# Memory.net
KiCad netlist of a schematic drawn in Altium Designer
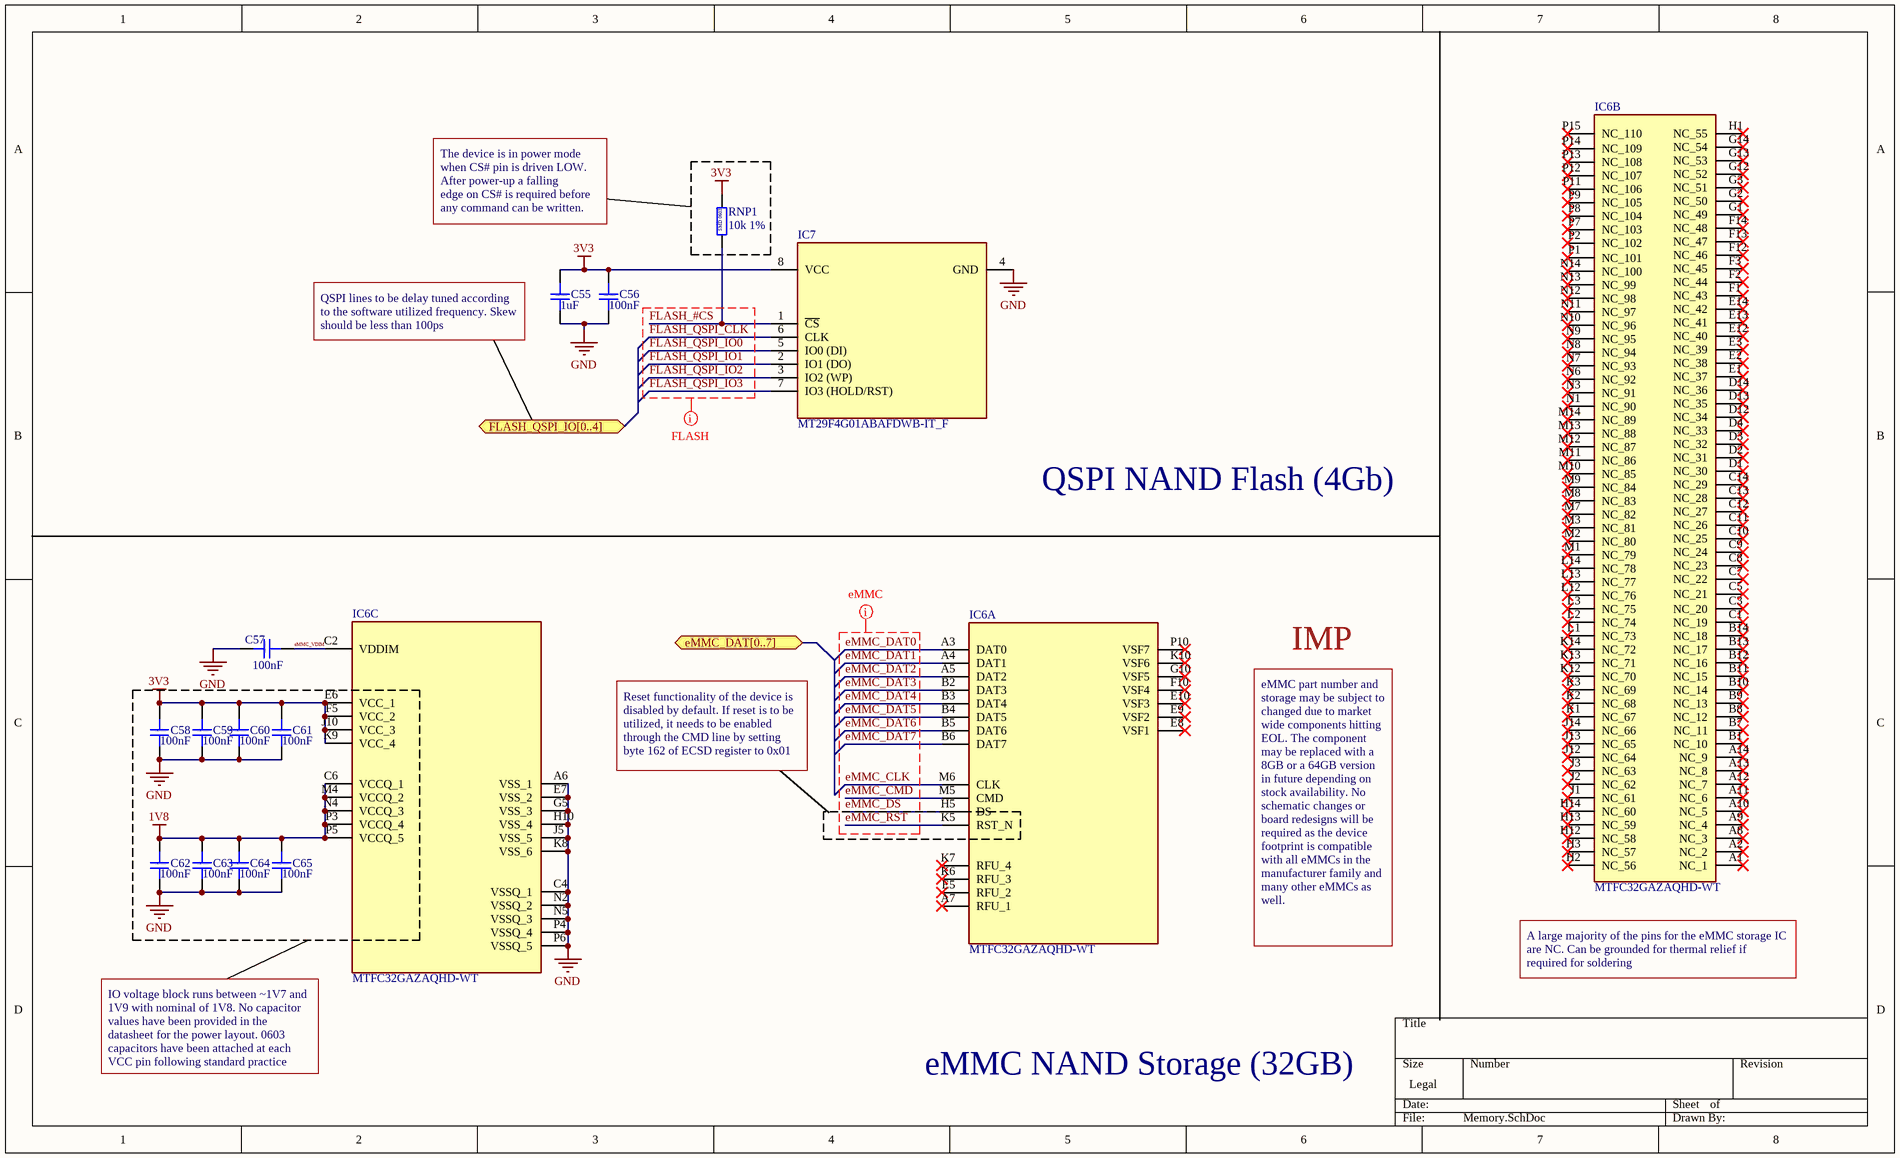
[diagram p0: Memory.SchDoc]

(export (version "E")
  (design (tool "Eeschema 10.0.6"))
  (components
    (comp (ref "C55")
      (value "1uF")
      (footprint "CAP_0402")
      (description "Capacitor SMD 0402 RATED")
      (libsource (lib "STeRG-Passives-Standard") (part "Capacitor-SMD-0402"))
    )
    (comp (ref "C56")
      (value "100nF")
      (footprint "CAP_0402")
      (description "Capacitor SMD 0402 RATED")
      (libsource (lib "STeRG-Passives-Standard") (part "Capacitor-SMD-0402"))
    )
    (comp (ref "C57")
      (value "100nF")
      (footprint "CAP_0402")
      (description "Capacitor SMD 0402 RATED")
      (libsource (lib "STeRG-Passives-Standard") (part "Capacitor-SMD-0402"))
    )
    (comp (ref "C58")
      (value "100nF")
      (footprint "CAP_0402")
      (description "Capacitor SMD 0402 RATED")
      (libsource (lib "STeRG-Passives-Standard") (part "Capacitor-SMD-0402"))
    )
    (comp (ref "C59")
      (value "100nF")
      (footprint "CAP_0402")
      (description "Capacitor SMD 0402 RATED")
      (libsource (lib "STeRG-Passives-Standard") (part "Capacitor-SMD-0402"))
    )
    (comp (ref "C60")
      (value "100nF")
      (footprint "CAP_0402")
      (description "Capacitor SMD 0402 RATED")
      (libsource (lib "STeRG-Passives-Standard") (part "Capacitor-SMD-0402"))
    )
    (comp (ref "C61")
      (value "100nF")
      (footprint "CAP_0402")
      (description "Capacitor SMD 0402 RATED")
      (libsource (lib "STeRG-Passives-Standard") (part "Capacitor-SMD-0402"))
    )
    (comp (ref "C62")
      (value "100nF")
      (footprint "CAP_0402")
      (description "Capacitor SMD 0402 RATED")
      (libsource (lib "STeRG-Passives-Standard") (part "Capacitor-SMD-0402"))
    )
    (comp (ref "C63")
      (value "100nF")
      (footprint "CAP_0402")
      (description "Capacitor SMD 0402 RATED")
      (libsource (lib "STeRG-Passives-Standard") (part "Capacitor-SMD-0402"))
    )
    (comp (ref "C64")
      (value "100nF")
      (footprint "CAP_0402")
      (description "Capacitor SMD 0402 RATED")
      (libsource (lib "STeRG-Passives-Standard") (part "Capacitor-SMD-0402"))
    )
    (comp (ref "C65")
      (value "100nF")
      (footprint "CAP_0402")
      (description "Capacitor SMD 0402 RATED")
      (libsource (lib "STeRG-Passives-Standard") (part "Capacitor-SMD-0402"))
    )
    (comp (ref "IC6")
      (value "MTFC32GAZAQHD-WT")
      (footprint "STeRG-ICs-Standard:BGA153C50P14X14_1150X1300X90")
      (description "Integrated Circuit")
      (fields (field (name "MOUSER PART NUMBER") "340-531307-TRAY"))
      (libsource (lib "") (part "MTFC32GAZAQHD-WT_1"))
    )
    (comp (ref "IC7")
      (value "MT29F4G01ABAFDWB-IT_F")
      (footprint "SON127P800X600X65-8N")
      (description "Integrated Circuit")
      (fields
        (field (name "MANUFACTURER_PART_NUMBER") "MT29F4G01ABAFDWB-IT:F")
        (field (name "MOUSER PART NUMBER") "340-359563")
      )
      (libsource (lib "STeRG-ICs-Standard") (part "MT29F4G01ABAFDWB-IT_F"))
    )
    (comp (ref "RNP1")
      (value "10k 1%")
      (footprint "RES_0603")
      (description "Resistor SMD 0603 RATED")
      (libsource (lib "STeRG-Passives-Standard") (part "Resistor-SMD-0603"))
    )
  )
  (nets
    (net (code "2") (name "/FLASH_#CS") (class "Default")
      (node (ref "IC7") (pin "1") (pinfunction "~{CS}_1") (pintype "passive"))
      (node (ref "RNP1") (pin "1") (pinfunction "1_1") (pintype "passive"))
    )
    (net (code "3") (name "/FLASH_QSPI_CLK") (class "Default")
      (node (ref "IC7") (pin "6") (pinfunction "CLK_6") (pintype "passive"))
    )
    (net (code "4") (name "/FLASH_QSPI_IO0") (class "Default")
      (node (ref "IC7") (pin "5") (pinfunction "IO0_(DI)_5") (pintype "passive"))
    )
    (net (code "5") (name "/FLASH_QSPI_IO1") (class "Default")
      (node (ref "IC7") (pin "2") (pinfunction "IO1_(DO)_2") (pintype "passive"))
    )
    (net (code "6") (name "/FLASH_QSPI_IO2") (class "Default")
      (node (ref "IC7") (pin "3") (pinfunction "IO2_(WP)_3") (pintype "passive"))
    )
    (net (code "7") (name "/FLASH_QSPI_IO3") (class "Default")
      (node (ref "IC7") (pin "7") (pinfunction "IO3_(HOLD/RST)_7") (pintype "passive"))
    )
    (net (code "9") (name "/eMMC_CLK") (class "Default")
      (node (ref "IC6") (pin "M6") (pinfunction "CLK_M6") (pintype "passive"))
    )
    (net (code "10") (name "/eMMC_CMD") (class "Default")
      (node (ref "IC6") (pin "M5") (pinfunction "CMD_M5") (pintype "passive"))
    )
    (net (code "11") (name "/eMMC_DAT0") (class "Default")
      (node (ref "IC6") (pin "A3") (pinfunction "DAT0_A3") (pintype "passive"))
    )
    (net (code "12") (name "/eMMC_DAT1") (class "Default")
      (node (ref "IC6") (pin "A4") (pinfunction "DAT1_A4") (pintype "passive"))
    )
    (net (code "13") (name "/eMMC_DAT2") (class "Default")
      (node (ref "IC6") (pin "A5") (pinfunction "DAT2_A5") (pintype "passive"))
    )
    (net (code "14") (name "/eMMC_DAT3") (class "Default")
      (node (ref "IC6") (pin "B2") (pinfunction "DAT3_B2") (pintype "passive"))
    )
    (net (code "15") (name "/eMMC_DAT4") (class "Default")
      (node (ref "IC6") (pin "B3") (pinfunction "DAT4_B3") (pintype "passive"))
    )
    (net (code "16") (name "/eMMC_DAT5") (class "Default")
      (node (ref "IC6") (pin "B4") (pinfunction "DAT5_B4") (pintype "passive"))
    )
    (net (code "17") (name "/eMMC_DAT6") (class "Default")
      (node (ref "IC6") (pin "B5") (pinfunction "DAT6_B5") (pintype "passive"))
    )
    (net (code "18") (name "/eMMC_DAT7") (class "Default")
      (node (ref "IC6") (pin "B6") (pinfunction "DAT7_B6") (pintype "passive"))
    )
    (net (code "20") (name "/eMMC_DS") (class "Default")
      (node (ref "IC6") (pin "H5") (pinfunction "DS_H5") (pintype "passive"))
    )
    (net (code "21") (name "/eMMC_RST") (class "Default")
      (node (ref "IC6") (pin "K5") (pinfunction "RST_N_K5") (pintype "passive"))
    )
    (net (code "22") (name "/eMMC_VDIM") (class "Default")
      (node (ref "C57") (pin "2") (pinfunction "2_2") (pintype "passive"))
      (node (ref "IC6") (pin "C2") (pinfunction "VDDIM_C2") (pintype "passive"))
    )
    (net (code "23") (name "1V8") (class "Default")
      (node (ref "C62") (pin "1") (pinfunction "1_1") (pintype "passive"))
      (node (ref "C63") (pin "1") (pinfunction "1_1") (pintype "passive"))
      (node (ref "C64") (pin "1") (pinfunction "1_1") (pintype "passive"))
      (node (ref "C65") (pin "1") (pinfunction "1_1") (pintype "passive"))
      (node (ref "IC6") (pin "C6") (pinfunction "VCCQ_1_C6") (pintype "passive"))
      (node (ref "IC6") (pin "M4") (pinfunction "VCCQ_2_M4") (pintype "passive"))
      (node (ref "IC6") (pin "N4") (pinfunction "VCCQ_3_N4") (pintype "passive"))
      (node (ref "IC6") (pin "P3") (pinfunction "VCCQ_4_P3") (pintype "passive"))
      (node (ref "IC6") (pin "P5") (pinfunction "VCCQ_5_P5") (pintype "passive"))
    )
    (net (code "24") (name "3V3") (class "Default")
      (node (ref "C55") (pin "1") (pinfunction "1_1") (pintype "passive"))
      (node (ref "C56") (pin "1") (pinfunction "1_1") (pintype "passive"))
      (node (ref "C58") (pin "1") (pinfunction "1_1") (pintype "passive"))
      (node (ref "C59") (pin "1") (pinfunction "1_1") (pintype "passive"))
      (node (ref "C60") (pin "1") (pinfunction "1_1") (pintype "passive"))
      (node (ref "C61") (pin "1") (pinfunction "1_1") (pintype "passive"))
      (node (ref "IC6") (pin "E6") (pinfunction "VCC_1_E6") (pintype "passive"))
      (node (ref "IC6") (pin "F5") (pinfunction "VCC_2_F5") (pintype "passive"))
      (node (ref "IC6") (pin "J10") (pinfunction "VCC_3_J10") (pintype "passive"))
      (node (ref "IC6") (pin "K9") (pinfunction "VCC_4_K9") (pintype "passive"))
      (node (ref "IC7") (pin "8") (pinfunction "VCC_8") (pintype "passive"))
      (node (ref "RNP1") (pin "2") (pinfunction "2_2") (pintype "passive"))
    )
    (net (code "25") (name "GND") (class "Default")
      (node (ref "C55") (pin "2") (pinfunction "2_2") (pintype "passive"))
      (node (ref "C56") (pin "2") (pinfunction "2_2") (pintype "passive"))
      (node (ref "C57") (pin "1") (pinfunction "1_1") (pintype "passive"))
      (node (ref "C58") (pin "2") (pinfunction "2_2") (pintype "passive"))
      (node (ref "C59") (pin "2") (pinfunction "2_2") (pintype "passive"))
      (node (ref "C60") (pin "2") (pinfunction "2_2") (pintype "passive"))
      (node (ref "C61") (pin "2") (pinfunction "2_2") (pintype "passive"))
      (node (ref "C62") (pin "2") (pinfunction "2_2") (pintype "passive"))
      (node (ref "C63") (pin "2") (pinfunction "2_2") (pintype "passive"))
      (node (ref "C64") (pin "2") (pinfunction "2_2") (pintype "passive"))
      (node (ref "C65") (pin "2") (pinfunction "2_2") (pintype "passive"))
      (node (ref "IC6") (pin "A6") (pinfunction "VSS_1_A6") (pintype "passive"))
      (node (ref "IC6") (pin "C4") (pinfunction "VSSQ_1_C4") (pintype "passive"))
      (node (ref "IC6") (pin "E7") (pinfunction "VSS_2_E7") (pintype "passive"))
      (node (ref "IC6") (pin "G5") (pinfunction "VSS_3_G5") (pintype "passive"))
      (node (ref "IC6") (pin "H10") (pinfunction "VSS_4_H10") (pintype "passive"))
      (node (ref "IC6") (pin "J5") (pinfunction "VSS_5_J5") (pintype "passive"))
      (node (ref "IC6") (pin "K8") (pinfunction "VSS_6_K8") (pintype "passive"))
      (node (ref "IC6") (pin "N2") (pinfunction "VSSQ_2_N2") (pintype "passive"))
      (node (ref "IC6") (pin "N5") (pinfunction "VSSQ_3_N5") (pintype "passive"))
      (node (ref "IC6") (pin "P4") (pinfunction "VSSQ_4_P4") (pintype "passive"))
      (node (ref "IC6") (pin "P6") (pinfunction "VSSQ_5_P6") (pintype "passive"))
      (node (ref "IC7") (pin "4") (pinfunction "GND_4") (pintype "passive"))
    )
    (net (code "26") (name "unconnected-(IC6A-RFU_1-PadA7)") (class "Default")
      (node (ref "IC6") (pin "A7") (pinfunction "RFU_1_A7") (pintype "passive+no_connect"))
    )
    (net (code "27") (name "unconnected-(IC6A-RFU_2-PadE5)") (class "Default")
      (node (ref "IC6") (pin "E5") (pinfunction "RFU_2_E5") (pintype "passive+no_connect"))
    )
    (net (code "28") (name "unconnected-(IC6A-RFU_3-PadK6)") (class "Default")
      (node (ref "IC6") (pin "K6") (pinfunction "RFU_3_K6") (pintype "passive+no_connect"))
    )
    (net (code "29") (name "unconnected-(IC6A-RFU_4-PadK7)") (class "Default")
      (node (ref "IC6") (pin "K7") (pinfunction "RFU_4_K7") (pintype "passive+no_connect"))
    )
    (net (code "30") (name "unconnected-(IC6A-VSF1-PadE8)") (class "Default")
      (node (ref "IC6") (pin "E8") (pinfunction "VSF1_E8") (pintype "passive+no_connect"))
    )
    (net (code "31") (name "unconnected-(IC6A-VSF2-PadE9)") (class "Default")
      (node (ref "IC6") (pin "E9") (pinfunction "VSF2_E9") (pintype "passive+no_connect"))
    )
    (net (code "32") (name "unconnected-(IC6A-VSF3-PadE10)") (class "Default")
      (node (ref "IC6") (pin "E10") (pinfunction "VSF3_E10") (pintype "passive+no_connect"))
    )
    (net (code "33") (name "unconnected-(IC6A-VSF4-PadF10)") (class "Default")
      (node (ref "IC6") (pin "F10") (pinfunction "VSF4_F10") (pintype "passive+no_connect"))
    )
    (net (code "34") (name "unconnected-(IC6A-VSF5-PadG10)") (class "Default")
      (node (ref "IC6") (pin "G10") (pinfunction "VSF5_G10") (pintype "passive+no_connect"))
    )
    (net (code "35") (name "unconnected-(IC6A-VSF6-PadK10)") (class "Default")
      (node (ref "IC6") (pin "K10") (pinfunction "VSF6_K10") (pintype "passive+no_connect"))
    )
    (net (code "36") (name "unconnected-(IC6A-VSF7-PadP10)") (class "Default")
      (node (ref "IC6") (pin "P10") (pinfunction "VSF7_P10") (pintype "passive+no_connect"))
    )
    (net (code "37") (name "unconnected-(IC6B-NC_1-PadA1)") (class "Default")
      (node (ref "IC6") (pin "A1") (pinfunction "NC_1_A1") (pintype "passive+no_connect"))
    )
    (net (code "38") (name "unconnected-(IC6B-NC_2-PadA2)") (class "Default")
      (node (ref "IC6") (pin "A2") (pinfunction "NC_2_A2") (pintype "passive+no_connect"))
    )
    (net (code "39") (name "unconnected-(IC6B-NC_3-PadA8)") (class "Default")
      (node (ref "IC6") (pin "A8") (pinfunction "NC_3_A8") (pintype "passive+no_connect"))
    )
    (net (code "40") (name "unconnected-(IC6B-NC_4-PadA9)") (class "Default")
      (node (ref "IC6") (pin "A9") (pinfunction "NC_4_A9") (pintype "passive+no_connect"))
    )
    (net (code "41") (name "unconnected-(IC6B-NC_5-PadA10)") (class "Default")
      (node (ref "IC6") (pin "A10") (pinfunction "NC_5_A10") (pintype "passive+no_connect"))
    )
    (net (code "42") (name "unconnected-(IC6B-NC_6-PadA11)") (class "Default")
      (node (ref "IC6") (pin "A11") (pinfunction "NC_6_A11") (pintype "passive+no_connect"))
    )
    (net (code "43") (name "unconnected-(IC6B-NC_7-PadA12)") (class "Default")
      (node (ref "IC6") (pin "A12") (pinfunction "NC_7_A12") (pintype "passive+no_connect"))
    )
    (net (code "44") (name "unconnected-(IC6B-NC_8-PadA13)") (class "Default")
      (node (ref "IC6") (pin "A13") (pinfunction "NC_8_A13") (pintype "passive+no_connect"))
    )
    (net (code "45") (name "unconnected-(IC6B-NC_9-PadA14)") (class "Default")
      (node (ref "IC6") (pin "A14") (pinfunction "NC_9_A14") (pintype "passive+no_connect"))
    )
    (net (code "46") (name "unconnected-(IC6B-NC_10-PadB1)") (class "Default")
      (node (ref "IC6") (pin "B1") (pinfunction "NC_10_B1") (pintype "passive+no_connect"))
    )
    (net (code "47") (name "unconnected-(IC6B-NC_11-PadB7)") (class "Default")
      (node (ref "IC6") (pin "B7") (pinfunction "NC_11_B7") (pintype "passive+no_connect"))
    )
    (net (code "48") (name "unconnected-(IC6B-NC_12-PadB8)") (class "Default")
      (node (ref "IC6") (pin "B8") (pinfunction "NC_12_B8") (pintype "passive+no_connect"))
    )
    (net (code "49") (name "unconnected-(IC6B-NC_13-PadB9)") (class "Default")
      (node (ref "IC6") (pin "B9") (pinfunction "NC_13_B9") (pintype "passive+no_connect"))
    )
    (net (code "50") (name "unconnected-(IC6B-NC_14-PadB10)") (class "Default")
      (node (ref "IC6") (pin "B10") (pinfunction "NC_14_B10") (pintype "passive+no_connect"))
    )
    (net (code "51") (name "unconnected-(IC6B-NC_15-PadB11)") (class "Default")
      (node (ref "IC6") (pin "B11") (pinfunction "NC_15_B11") (pintype "passive+no_connect"))
    )
    (net (code "52") (name "unconnected-(IC6B-NC_16-PadB12)") (class "Default")
      (node (ref "IC6") (pin "B12") (pinfunction "NC_16_B12") (pintype "passive+no_connect"))
    )
    (net (code "53") (name "unconnected-(IC6B-NC_17-PadB13)") (class "Default")
      (node (ref "IC6") (pin "B13") (pinfunction "NC_17_B13") (pintype "passive+no_connect"))
    )
    (net (code "54") (name "unconnected-(IC6B-NC_18-PadB14)") (class "Default")
      (node (ref "IC6") (pin "B14") (pinfunction "NC_18_B14") (pintype "passive+no_connect"))
    )
    (net (code "55") (name "unconnected-(IC6B-NC_19-PadC1)") (class "Default")
      (node (ref "IC6") (pin "C1") (pinfunction "NC_19_C1") (pintype "passive+no_connect"))
    )
    (net (code "56") (name "unconnected-(IC6B-NC_20-PadC3)") (class "Default")
      (node (ref "IC6") (pin "C3") (pinfunction "NC_20_C3") (pintype "passive+no_connect"))
    )
    (net (code "57") (name "unconnected-(IC6B-NC_21-PadC5)") (class "Default")
      (node (ref "IC6") (pin "C5") (pinfunction "NC_21_C5") (pintype "passive+no_connect"))
    )
    (net (code "58") (name "unconnected-(IC6B-NC_22-PadC7)") (class "Default")
      (node (ref "IC6") (pin "C7") (pinfunction "NC_22_C7") (pintype "passive+no_connect"))
    )
    (net (code "59") (name "unconnected-(IC6B-NC_23-PadC8)") (class "Default")
      (node (ref "IC6") (pin "C8") (pinfunction "NC_23_C8") (pintype "passive+no_connect"))
    )
    (net (code "60") (name "unconnected-(IC6B-NC_24-PadC9)") (class "Default")
      (node (ref "IC6") (pin "C9") (pinfunction "NC_24_C9") (pintype "passive+no_connect"))
    )
    (net (code "61") (name "unconnected-(IC6B-NC_25-PadC10)") (class "Default")
      (node (ref "IC6") (pin "C10") (pinfunction "NC_25_C10") (pintype "passive+no_connect"))
    )
    (net (code "62") (name "unconnected-(IC6B-NC_26-PadC11)") (class "Default")
      (node (ref "IC6") (pin "C11") (pinfunction "NC_26_C11") (pintype "passive+no_connect"))
    )
    (net (code "63") (name "unconnected-(IC6B-NC_27-PadC12)") (class "Default")
      (node (ref "IC6") (pin "C12") (pinfunction "NC_27_C12") (pintype "passive+no_connect"))
    )
    (net (code "64") (name "unconnected-(IC6B-NC_28-PadC13)") (class "Default")
      (node (ref "IC6") (pin "C13") (pinfunction "NC_28_C13") (pintype "passive+no_connect"))
    )
    (net (code "65") (name "unconnected-(IC6B-NC_29-PadC14)") (class "Default")
      (node (ref "IC6") (pin "C14") (pinfunction "NC_29_C14") (pintype "passive+no_connect"))
    )
    (net (code "66") (name "unconnected-(IC6B-NC_30-PadD1)") (class "Default")
      (node (ref "IC6") (pin "D1") (pinfunction "NC_30_D1") (pintype "passive+no_connect"))
    )
    (net (code "67") (name "unconnected-(IC6B-NC_31-PadD2)") (class "Default")
      (node (ref "IC6") (pin "D2") (pinfunction "NC_31_D2") (pintype "passive+no_connect"))
    )
    (net (code "68") (name "unconnected-(IC6B-NC_32-PadD3)") (class "Default")
      (node (ref "IC6") (pin "D3") (pinfunction "NC_32_D3") (pintype "passive+no_connect"))
    )
    (net (code "69") (name "unconnected-(IC6B-NC_33-PadD4)") (class "Default")
      (node (ref "IC6") (pin "D4") (pinfunction "NC_33_D4") (pintype "passive+no_connect"))
    )
    (net (code "70") (name "unconnected-(IC6B-NC_34-PadD12)") (class "Default")
      (node (ref "IC6") (pin "D12") (pinfunction "NC_34_D12") (pintype "passive+no_connect"))
    )
    (net (code "71") (name "unconnected-(IC6B-NC_35-PadD13)") (class "Default")
      (node (ref "IC6") (pin "D13") (pinfunction "NC_35_D13") (pintype "passive+no_connect"))
    )
    (net (code "72") (name "unconnected-(IC6B-NC_36-PadD14)") (class "Default")
      (node (ref "IC6") (pin "D14") (pinfunction "NC_36_D14") (pintype "passive+no_connect"))
    )
    (net (code "73") (name "unconnected-(IC6B-NC_37-PadE1)") (class "Default")
      (node (ref "IC6") (pin "E1") (pinfunction "NC_37_E1") (pintype "passive+no_connect"))
    )
    (net (code "74") (name "unconnected-(IC6B-NC_38-PadE2)") (class "Default")
      (node (ref "IC6") (pin "E2") (pinfunction "NC_38_E2") (pintype "passive+no_connect"))
    )
    (net (code "75") (name "unconnected-(IC6B-NC_39-PadE3)") (class "Default")
      (node (ref "IC6") (pin "E3") (pinfunction "NC_39_E3") (pintype "passive+no_connect"))
    )
    (net (code "76") (name "unconnected-(IC6B-NC_40-PadE12)") (class "Default")
      (node (ref "IC6") (pin "E12") (pinfunction "NC_40_E12") (pintype "passive+no_connect"))
    )
    (net (code "77") (name "unconnected-(IC6B-NC_41-PadE13)") (class "Default")
      (node (ref "IC6") (pin "E13") (pinfunction "NC_41_E13") (pintype "passive+no_connect"))
    )
    (net (code "78") (name "unconnected-(IC6B-NC_42-PadE14)") (class "Default")
      (node (ref "IC6") (pin "E14") (pinfunction "NC_42_E14") (pintype "passive+no_connect"))
    )
    (net (code "79") (name "unconnected-(IC6B-NC_43-PadF1)") (class "Default")
      (node (ref "IC6") (pin "F1") (pinfunction "NC_43_F1") (pintype "passive+no_connect"))
    )
    (net (code "80") (name "unconnected-(IC6B-NC_44-PadF2)") (class "Default")
      (node (ref "IC6") (pin "F2") (pinfunction "NC_44_F2") (pintype "passive+no_connect"))
    )
    (net (code "81") (name "unconnected-(IC6B-NC_45-PadF3)") (class "Default")
      (node (ref "IC6") (pin "F3") (pinfunction "NC_45_F3") (pintype "passive+no_connect"))
    )
    (net (code "82") (name "unconnected-(IC6B-NC_46-PadF12)") (class "Default")
      (node (ref "IC6") (pin "F12") (pinfunction "NC_46_F12") (pintype "passive+no_connect"))
    )
    (net (code "83") (name "unconnected-(IC6B-NC_47-PadF13)") (class "Default")
      (node (ref "IC6") (pin "F13") (pinfunction "NC_47_F13") (pintype "passive+no_connect"))
    )
    (net (code "84") (name "unconnected-(IC6B-NC_48-PadF14)") (class "Default")
      (node (ref "IC6") (pin "F14") (pinfunction "NC_48_F14") (pintype "passive+no_connect"))
    )
    (net (code "85") (name "unconnected-(IC6B-NC_49-PadG1)") (class "Default")
      (node (ref "IC6") (pin "G1") (pinfunction "NC_49_G1") (pintype "passive+no_connect"))
    )
    (net (code "86") (name "unconnected-(IC6B-NC_50-PadG2)") (class "Default")
      (node (ref "IC6") (pin "G2") (pinfunction "NC_50_G2") (pintype "passive+no_connect"))
    )
    (net (code "87") (name "unconnected-(IC6B-NC_51-PadG3)") (class "Default")
      (node (ref "IC6") (pin "G3") (pinfunction "NC_51_G3") (pintype "passive+no_connect"))
    )
    (net (code "88") (name "unconnected-(IC6B-NC_52-PadG12)") (class "Default")
      (node (ref "IC6") (pin "G12") (pinfunction "NC_52_G12") (pintype "passive+no_connect"))
    )
    (net (code "89") (name "unconnected-(IC6B-NC_53-PadG13)") (class "Default")
      (node (ref "IC6") (pin "G13") (pinfunction "NC_53_G13") (pintype "passive+no_connect"))
    )
    (net (code "90") (name "unconnected-(IC6B-NC_54-PadG14)") (class "Default")
      (node (ref "IC6") (pin "G14") (pinfunction "NC_54_G14") (pintype "passive+no_connect"))
    )
    (net (code "91") (name "unconnected-(IC6B-NC_55-PadH1)") (class "Default")
      (node (ref "IC6") (pin "H1") (pinfunction "NC_55_H1") (pintype "passive+no_connect"))
    )
    (net (code "92") (name "unconnected-(IC6B-NC_56-PadH2)") (class "Default")
      (node (ref "IC6") (pin "H2") (pinfunction "NC_56_H2") (pintype "passive+no_connect"))
    )
    (net (code "93") (name "unconnected-(IC6B-NC_57-PadH3)") (class "Default")
      (node (ref "IC6") (pin "H3") (pinfunction "NC_57_H3") (pintype "passive+no_connect"))
    )
    (net (code "94") (name "unconnected-(IC6B-NC_58-PadH12)") (class "Default")
      (node (ref "IC6") (pin "H12") (pinfunction "NC_58_H12") (pintype "passive+no_connect"))
    )
    (net (code "95") (name "unconnected-(IC6B-NC_59-PadH13)") (class "Default")
      (node (ref "IC6") (pin "H13") (pinfunction "NC_59_H13") (pintype "passive+no_connect"))
    )
    (net (code "96") (name "unconnected-(IC6B-NC_60-PadH14)") (class "Default")
      (node (ref "IC6") (pin "H14") (pinfunction "NC_60_H14") (pintype "passive+no_connect"))
    )
    (net (code "97") (name "unconnected-(IC6B-NC_61-PadJ1)") (class "Default")
      (node (ref "IC6") (pin "J1") (pinfunction "NC_61_J1") (pintype "passive+no_connect"))
    )
    (net (code "98") (name "unconnected-(IC6B-NC_62-PadJ2)") (class "Default")
      (node (ref "IC6") (pin "J2") (pinfunction "NC_62_J2") (pintype "passive+no_connect"))
    )
    (net (code "99") (name "unconnected-(IC6B-NC_63-PadJ3)") (class "Default")
      (node (ref "IC6") (pin "J3") (pinfunction "NC_63_J3") (pintype "passive+no_connect"))
    )
    (net (code "100") (name "unconnected-(IC6B-NC_64-PadJ12)") (class "Default")
      (node (ref "IC6") (pin "J12") (pinfunction "NC_64_J12") (pintype "passive+no_connect"))
    )
    (net (code "101") (name "unconnected-(IC6B-NC_65-PadJ13)") (class "Default")
      (node (ref "IC6") (pin "J13") (pinfunction "NC_65_J13") (pintype "passive+no_connect"))
    )
    (net (code "102") (name "unconnected-(IC6B-NC_66-PadJ14)") (class "Default")
      (node (ref "IC6") (pin "J14") (pinfunction "NC_66_J14") (pintype "passive+no_connect"))
    )
    (net (code "103") (name "unconnected-(IC6B-NC_67-PadK1)") (class "Default")
      (node (ref "IC6") (pin "K1") (pinfunction "NC_67_K1") (pintype "passive+no_connect"))
    )
    (net (code "104") (name "unconnected-(IC6B-NC_68-PadK2)") (class "Default")
      (node (ref "IC6") (pin "K2") (pinfunction "NC_68_K2") (pintype "passive+no_connect"))
    )
    (net (code "105") (name "unconnected-(IC6B-NC_69-PadK3)") (class "Default")
      (node (ref "IC6") (pin "K3") (pinfunction "NC_69_K3") (pintype "passive+no_connect"))
    )
    (net (code "106") (name "unconnected-(IC6B-NC_70-PadK12)") (class "Default")
      (node (ref "IC6") (pin "K12") (pinfunction "NC_70_K12") (pintype "passive+no_connect"))
    )
    (net (code "107") (name "unconnected-(IC6B-NC_71-PadK13)") (class "Default")
      (node (ref "IC6") (pin "K13") (pinfunction "NC_71_K13") (pintype "passive+no_connect"))
    )
    (net (code "108") (name "unconnected-(IC6B-NC_72-PadK14)") (class "Default")
      (node (ref "IC6") (pin "K14") (pinfunction "NC_72_K14") (pintype "passive+no_connect"))
    )
    (net (code "109") (name "unconnected-(IC6B-NC_73-PadL1)") (class "Default")
      (node (ref "IC6") (pin "L1") (pinfunction "NC_73_L1") (pintype "passive+no_connect"))
    )
    (net (code "110") (name "unconnected-(IC6B-NC_74-PadL2)") (class "Default")
      (node (ref "IC6") (pin "L2") (pinfunction "NC_74_L2") (pintype "passive+no_connect"))
    )
    (net (code "111") (name "unconnected-(IC6B-NC_75-PadL3)") (class "Default")
      (node (ref "IC6") (pin "L3") (pinfunction "NC_75_L3") (pintype "passive+no_connect"))
    )
    (net (code "112") (name "unconnected-(IC6B-NC_76-PadL12)") (class "Default")
      (node (ref "IC6") (pin "L12") (pinfunction "NC_76_L12") (pintype "passive+no_connect"))
    )
    (net (code "113") (name "unconnected-(IC6B-NC_77-PadL13)") (class "Default")
      (node (ref "IC6") (pin "L13") (pinfunction "NC_77_L13") (pintype "passive+no_connect"))
    )
    (net (code "114") (name "unconnected-(IC6B-NC_78-PadL14)") (class "Default")
      (node (ref "IC6") (pin "L14") (pinfunction "NC_78_L14") (pintype "passive+no_connect"))
    )
    (net (code "115") (name "unconnected-(IC6B-NC_79-PadM1)") (class "Default")
      (node (ref "IC6") (pin "M1") (pinfunction "NC_79_M1") (pintype "passive+no_connect"))
    )
    (net (code "116") (name "unconnected-(IC6B-NC_80-PadM2)") (class "Default")
      (node (ref "IC6") (pin "M2") (pinfunction "NC_80_M2") (pintype "passive+no_connect"))
    )
    (net (code "117") (name "unconnected-(IC6B-NC_81-PadM3)") (class "Default")
      (node (ref "IC6") (pin "M3") (pinfunction "NC_81_M3") (pintype "passive+no_connect"))
    )
    (net (code "118") (name "unconnected-(IC6B-NC_82-PadM7)") (class "Default")
      (node (ref "IC6") (pin "M7") (pinfunction "NC_82_M7") (pintype "passive+no_connect"))
    )
    (net (code "119") (name "unconnected-(IC6B-NC_83-PadM8)") (class "Default")
      (node (ref "IC6") (pin "M8") (pinfunction "NC_83_M8") (pintype "passive+no_connect"))
    )
    (net (code "120") (name "unconnected-(IC6B-NC_84-PadM9)") (class "Default")
      (node (ref "IC6") (pin "M9") (pinfunction "NC_84_M9") (pintype "passive+no_connect"))
    )
    (net (code "121") (name "unconnected-(IC6B-NC_85-PadM10)") (class "Default")
      (node (ref "IC6") (pin "M10") (pinfunction "NC_85_M10") (pintype "passive+no_connect"))
    )
    (net (code "122") (name "unconnected-(IC6B-NC_86-PadM11)") (class "Default")
      (node (ref "IC6") (pin "M11") (pinfunction "NC_86_M11") (pintype "passive+no_connect"))
    )
    (net (code "123") (name "unconnected-(IC6B-NC_87-PadM12)") (class "Default")
      (node (ref "IC6") (pin "M12") (pinfunction "NC_87_M12") (pintype "passive+no_connect"))
    )
    (net (code "124") (name "unconnected-(IC6B-NC_88-PadM13)") (class "Default")
      (node (ref "IC6") (pin "M13") (pinfunction "NC_88_M13") (pintype "passive+no_connect"))
    )
    (net (code "125") (name "unconnected-(IC6B-NC_89-PadM14)") (class "Default")
      (node (ref "IC6") (pin "M14") (pinfunction "NC_89_M14") (pintype "passive+no_connect"))
    )
    (net (code "126") (name "unconnected-(IC6B-NC_90-PadN1)") (class "Default")
      (node (ref "IC6") (pin "N1") (pinfunction "NC_90_N1") (pintype "passive+no_connect"))
    )
    (net (code "127") (name "unconnected-(IC6B-NC_91-PadN3)") (class "Default")
      (node (ref "IC6") (pin "N3") (pinfunction "NC_91_N3") (pintype "passive+no_connect"))
    )
    (net (code "128") (name "unconnected-(IC6B-NC_92-PadN6)") (class "Default")
      (node (ref "IC6") (pin "N6") (pinfunction "NC_92_N6") (pintype "passive+no_connect"))
    )
    (net (code "129") (name "unconnected-(IC6B-NC_93-PadN7)") (class "Default")
      (node (ref "IC6") (pin "N7") (pinfunction "NC_93_N7") (pintype "passive+no_connect"))
    )
    (net (code "130") (name "unconnected-(IC6B-NC_94-PadN8)") (class "Default")
      (node (ref "IC6") (pin "N8") (pinfunction "NC_94_N8") (pintype "passive+no_connect"))
    )
    (net (code "131") (name "unconnected-(IC6B-NC_95-PadN9)") (class "Default")
      (node (ref "IC6") (pin "N9") (pinfunction "NC_95_N9") (pintype "passive+no_connect"))
    )
    (net (code "132") (name "unconnected-(IC6B-NC_96-PadN10)") (class "Default")
      (node (ref "IC6") (pin "N10") (pinfunction "NC_96_N10") (pintype "passive+no_connect"))
    )
    (net (code "133") (name "unconnected-(IC6B-NC_97-PadN11)") (class "Default")
      (node (ref "IC6") (pin "N11") (pinfunction "NC_97_N11") (pintype "passive+no_connect"))
    )
    (net (code "134") (name "unconnected-(IC6B-NC_98-PadN12)") (class "Default")
      (node (ref "IC6") (pin "N12") (pinfunction "NC_98_N12") (pintype "passive+no_connect"))
    )
    (net (code "135") (name "unconnected-(IC6B-NC_99-PadN13)") (class "Default")
      (node (ref "IC6") (pin "N13") (pinfunction "NC_99_N13") (pintype "passive+no_connect"))
    )
    (net (code "136") (name "unconnected-(IC6B-NC_100-PadN14)") (class "Default")
      (node (ref "IC6") (pin "N14") (pinfunction "NC_100_N14") (pintype "passive+no_connect"))
    )
    (net (code "137") (name "unconnected-(IC6B-NC_101-PadP1)") (class "Default")
      (node (ref "IC6") (pin "P1") (pinfunction "NC_101_P1") (pintype "passive+no_connect"))
    )
    (net (code "138") (name "unconnected-(IC6B-NC_102-PadP2)") (class "Default")
      (node (ref "IC6") (pin "P2") (pinfunction "NC_102_P2") (pintype "passive+no_connect"))
    )
    (net (code "139") (name "unconnected-(IC6B-NC_103-PadP7)") (class "Default")
      (node (ref "IC6") (pin "P7") (pinfunction "NC_103_P7") (pintype "passive+no_connect"))
    )
    (net (code "140") (name "unconnected-(IC6B-NC_104-PadP8)") (class "Default")
      (node (ref "IC6") (pin "P8") (pinfunction "NC_104_P8") (pintype "passive+no_connect"))
    )
    (net (code "141") (name "unconnected-(IC6B-NC_105-PadP9)") (class "Default")
      (node (ref "IC6") (pin "P9") (pinfunction "NC_105_P9") (pintype "passive+no_connect"))
    )
    (net (code "142") (name "unconnected-(IC6B-NC_106-PadP11)") (class "Default")
      (node (ref "IC6") (pin "P11") (pinfunction "NC_106_P11") (pintype "passive+no_connect"))
    )
    (net (code "143") (name "unconnected-(IC6B-NC_107-PadP12)") (class "Default")
      (node (ref "IC6") (pin "P12") (pinfunction "NC_107_P12") (pintype "passive+no_connect"))
    )
    (net (code "144") (name "unconnected-(IC6B-NC_108-PadP13)") (class "Default")
      (node (ref "IC6") (pin "P13") (pinfunction "NC_108_P13") (pintype "passive+no_connect"))
    )
    (net (code "145") (name "unconnected-(IC6B-NC_109-PadP14)") (class "Default")
      (node (ref "IC6") (pin "P14") (pinfunction "NC_109_P14") (pintype "passive+no_connect"))
    )
    (net (code "146") (name "unconnected-(IC6B-NC_110-PadP15)") (class "Default")
      (node (ref "IC6") (pin "P15") (pinfunction "NC_110_P15") (pintype "passive+no_connect"))
    )
  )
)
